# 5_-MCU_CONNECTORS.net
KiCad netlist of a schematic drawn in Altium Designer
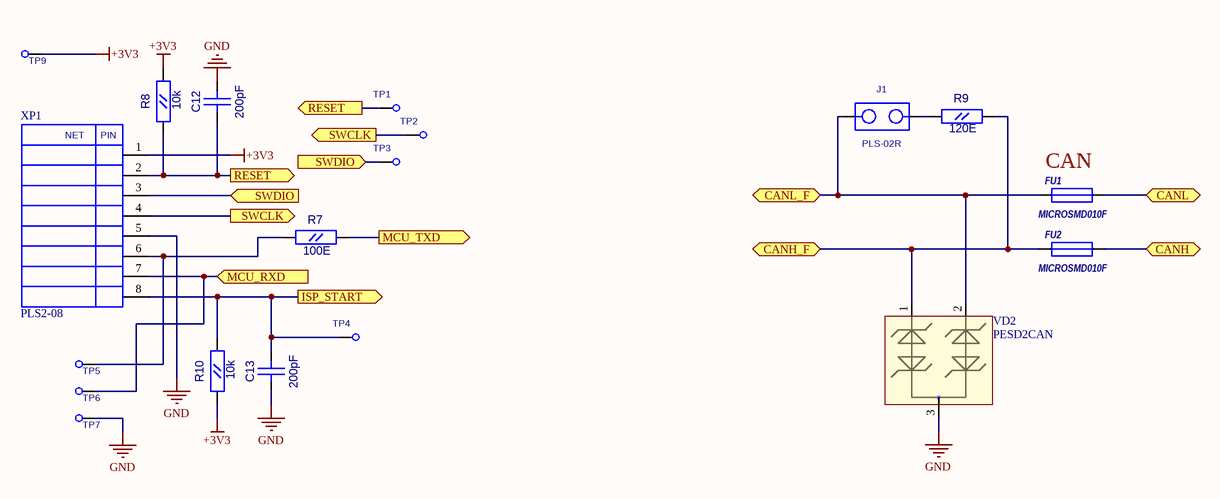
[diagram p0: [5]-MCU_CONNECTORS.SchDoc]

(export (version "E")
  (design (tool "Eeschema 10.0.6"))
  (components
    (comp (ref "C12")
      (value "200pF")
      (footprint "CC0603")
      (description "CC0603")
      (libsource (lib "gprs_modem_2") (part "CC0603"))
    )
    (comp (ref "C13")
      (value "200pF")
      (footprint "CC0603")
      (description "CC0603")
      (libsource (lib "gprs_modem_2") (part "CC0603"))
    )
    (comp (ref "FU1")
      (value "MICROSMD010F")
      (footprint "RC1210")
      (description "MICROSMD")
      (libsource (lib "gprs_modem_2") (part "MICROSMD"))
    )
    (comp (ref "FU2")
      (value "MICROSMD010F")
      (footprint "RC1210")
      (description "MICROSMD")
      (libsource (lib "gprs_modem_2") (part "MICROSMD"))
    )
    (comp (ref "J1")
      (value "PLS-02R")
      (footprint "PLS-02R")
      (libsource (lib "fizik_lib (1)") (part "PLS-02R"))
    )
    (comp (ref "R7")
      (value "100E")
      (footprint "RC0603")
      (description "RC0603")
      (libsource (lib "gprs_modem_2") (part "RC0603"))
    )
    (comp (ref "R8")
      (value "10k")
      (footprint "RC0603")
      (description "RC0603")
      (libsource (lib "gprs_modem_2") (part "RC0603"))
    )
    (comp (ref "R9")
      (value "120E")
      (footprint "RC0805")
      (description "RC0805")
      (libsource (lib "fizik_lib") (part "RC0805"))
    )
    (comp (ref "R10")
      (value "10k")
      (footprint "RC0603")
      (description "RC0603")
      (libsource (lib "gprs_modem_2") (part "RC0603"))
    )
    (comp (ref "TP1")
      (value "TESTPOINT1")
      (footprint "TESTPOINT1")
      (libsource (lib "fizik_lib (1)") (part "TESTPOINT1"))
    )
    (comp (ref "TP2")
      (value "TESTPOINT1")
      (footprint "TESTPOINT1")
      (libsource (lib "fizik_lib (1)") (part "TESTPOINT1"))
    )
    (comp (ref "TP3")
      (value "TESTPOINT1")
      (footprint "TESTPOINT1")
      (libsource (lib "fizik_lib (1)") (part "TESTPOINT1"))
    )
    (comp (ref "TP4")
      (value "TESTPOINT1")
      (footprint "TESTPOINT1")
      (libsource (lib "fizik_lib (1)") (part "TESTPOINT1"))
    )
    (comp (ref "TP5")
      (value "TESTPOINT1")
      (footprint "TESTPOINT1")
      (libsource (lib "fizik_lib (1)") (part "TESTPOINT1"))
    )
    (comp (ref "TP6")
      (value "TESTPOINT1")
      (footprint "TESTPOINT1")
      (libsource (lib "fizik_lib (1)") (part "TESTPOINT1"))
    )
    (comp (ref "TP7")
      (value "TESTPOINT1")
      (footprint "TESTPOINT1")
      (libsource (lib "fizik_lib (1)") (part "TESTPOINT1"))
    )
    (comp (ref "TP9")
      (value "TESTPOINT1")
      (footprint "TESTPOINT1")
      (libsource (lib "fizik_lib (1)") (part "TESTPOINT1"))
    )
    (comp (ref "VD2")
      (value "PESD2CAN")
      (footprint "SOT-23(123)")
      (description "TVS for CAN")
      (libsource (lib "gprs_modem_2") (part "PESD2CAN"))
    )
    (comp (ref "XP1") (value "PLS2-08") (footprint "PLS2-08") (libsource (lib "fizik_lib") (part "PLS2-08")))
  )
  (nets
    (net (code "1") (name "+3V3") (class "Default")
      (node (ref "R10") (pin "1") (pinfunction "A_1") (pintype "passive"))
      (node (ref "R8") (pin "2") (pinfunction "B_2") (pintype "passive"))
      (node (ref "TP9") (pin "1") (pintype "passive"))
      (node (ref "XP1") (pin "1") (pinfunction "1_1") (pintype "passive"))
    )
    (net (code "2") (name "/CANH") (class "Default") (node (ref "FU2") (pin "2") (pintype "passive")))
    (net (code "3") (name "/CANH_F") (class "Default")
      (node (ref "FU2") (pin "1") (pintype "passive"))
      (node (ref "R9") (pin "2") (pinfunction "B_2") (pintype "passive"))
      (node (ref "VD2") (pin "1") (pinfunction "1_1") (pintype "passive"))
    )
    (net (code "4") (name "/CANL") (class "Default") (node (ref "FU1") (pin "2") (pintype "passive")))
    (net (code "5") (name "/CANL_F") (class "Default")
      (node (ref "FU1") (pin "1") (pintype "passive"))
      (node (ref "J1") (pin "1") (pintype "passive"))
      (node (ref "VD2") (pin "2") (pinfunction "2_2") (pintype "passive"))
    )
    (net (code "6") (name "/ISP_START") (class "Default")
      (node (ref "C13") (pin "2") (pinfunction "B_2") (pintype "passive"))
      (node (ref "R10") (pin "2") (pinfunction "B_2") (pintype "passive"))
      (node (ref "TP4") (pin "1") (pintype "passive"))
      (node (ref "XP1") (pin "8") (pinfunction "8_8") (pintype "passive"))
    )
    (net (code "7") (name "/MCU_RXD") (class "Default")
      (node (ref "TP6") (pin "1") (pintype "passive"))
      (node (ref "XP1") (pin "7") (pinfunction "7_7") (pintype "passive"))
    )
    (net (code "8") (name "/MCU_TXD") (class "Default")
      (node (ref "R7") (pin "2") (pinfunction "B_2") (pintype "passive"))
    )
    (net (code "9") (name "/RESET") (class "Default")
      (node (ref "C12") (pin "1") (pinfunction "A_1") (pintype "passive"))
      (node (ref "R8") (pin "1") (pinfunction "A_1") (pintype "passive"))
      (node (ref "TP1") (pin "1") (pintype "passive"))
      (node (ref "XP1") (pin "2") (pinfunction "2_2") (pintype "passive"))
    )
    (net (code "10") (name "/SWCLK") (class "Default")
      (node (ref "TP2") (pin "1") (pintype "passive"))
      (node (ref "XP1") (pin "4") (pinfunction "4_4") (pintype "passive"))
    )
    (net (code "11") (name "/SWDIO") (class "Default")
      (node (ref "TP3") (pin "1") (pintype "passive"))
      (node (ref "XP1") (pin "3") (pinfunction "3_3") (pintype "passive"))
    )
    (net (code "12") (name "GND") (class "Default")
      (node (ref "C12") (pin "2") (pinfunction "B_2") (pintype "passive"))
      (node (ref "C13") (pin "1") (pinfunction "A_1") (pintype "passive"))
      (node (ref "TP7") (pin "1") (pintype "passive"))
      (node (ref "VD2") (pin "3") (pinfunction "3_3") (pintype "passive"))
      (node (ref "XP1") (pin "5") (pinfunction "5_5") (pintype "passive"))
    )
    (net (code "13") (name "Net-(R7-A)") (class "Default")
      (node (ref "R7") (pin "1") (pinfunction "A_1") (pintype "passive"))
      (node (ref "TP5") (pin "1") (pintype "passive"))
      (node (ref "XP1") (pin "6") (pinfunction "6_6") (pintype "passive"))
    )
    (net (code "14") (name "Net-(R9-A)") (class "Default")
      (node (ref "J1") (pin "2") (pintype "passive"))
      (node (ref "R9") (pin "1") (pinfunction "A_1") (pintype "passive"))
    )
  )
)
